# SonoluxV1.net
KiCad netlist of a schematic drawn in EAGLE
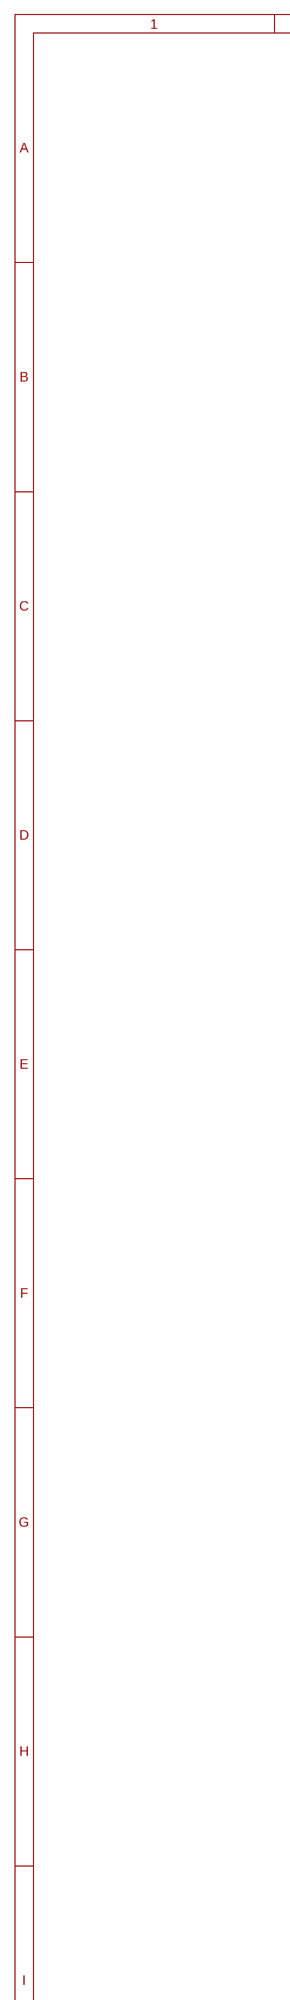
[diagram p0: schematic, sheet 1, part 1 of 2]
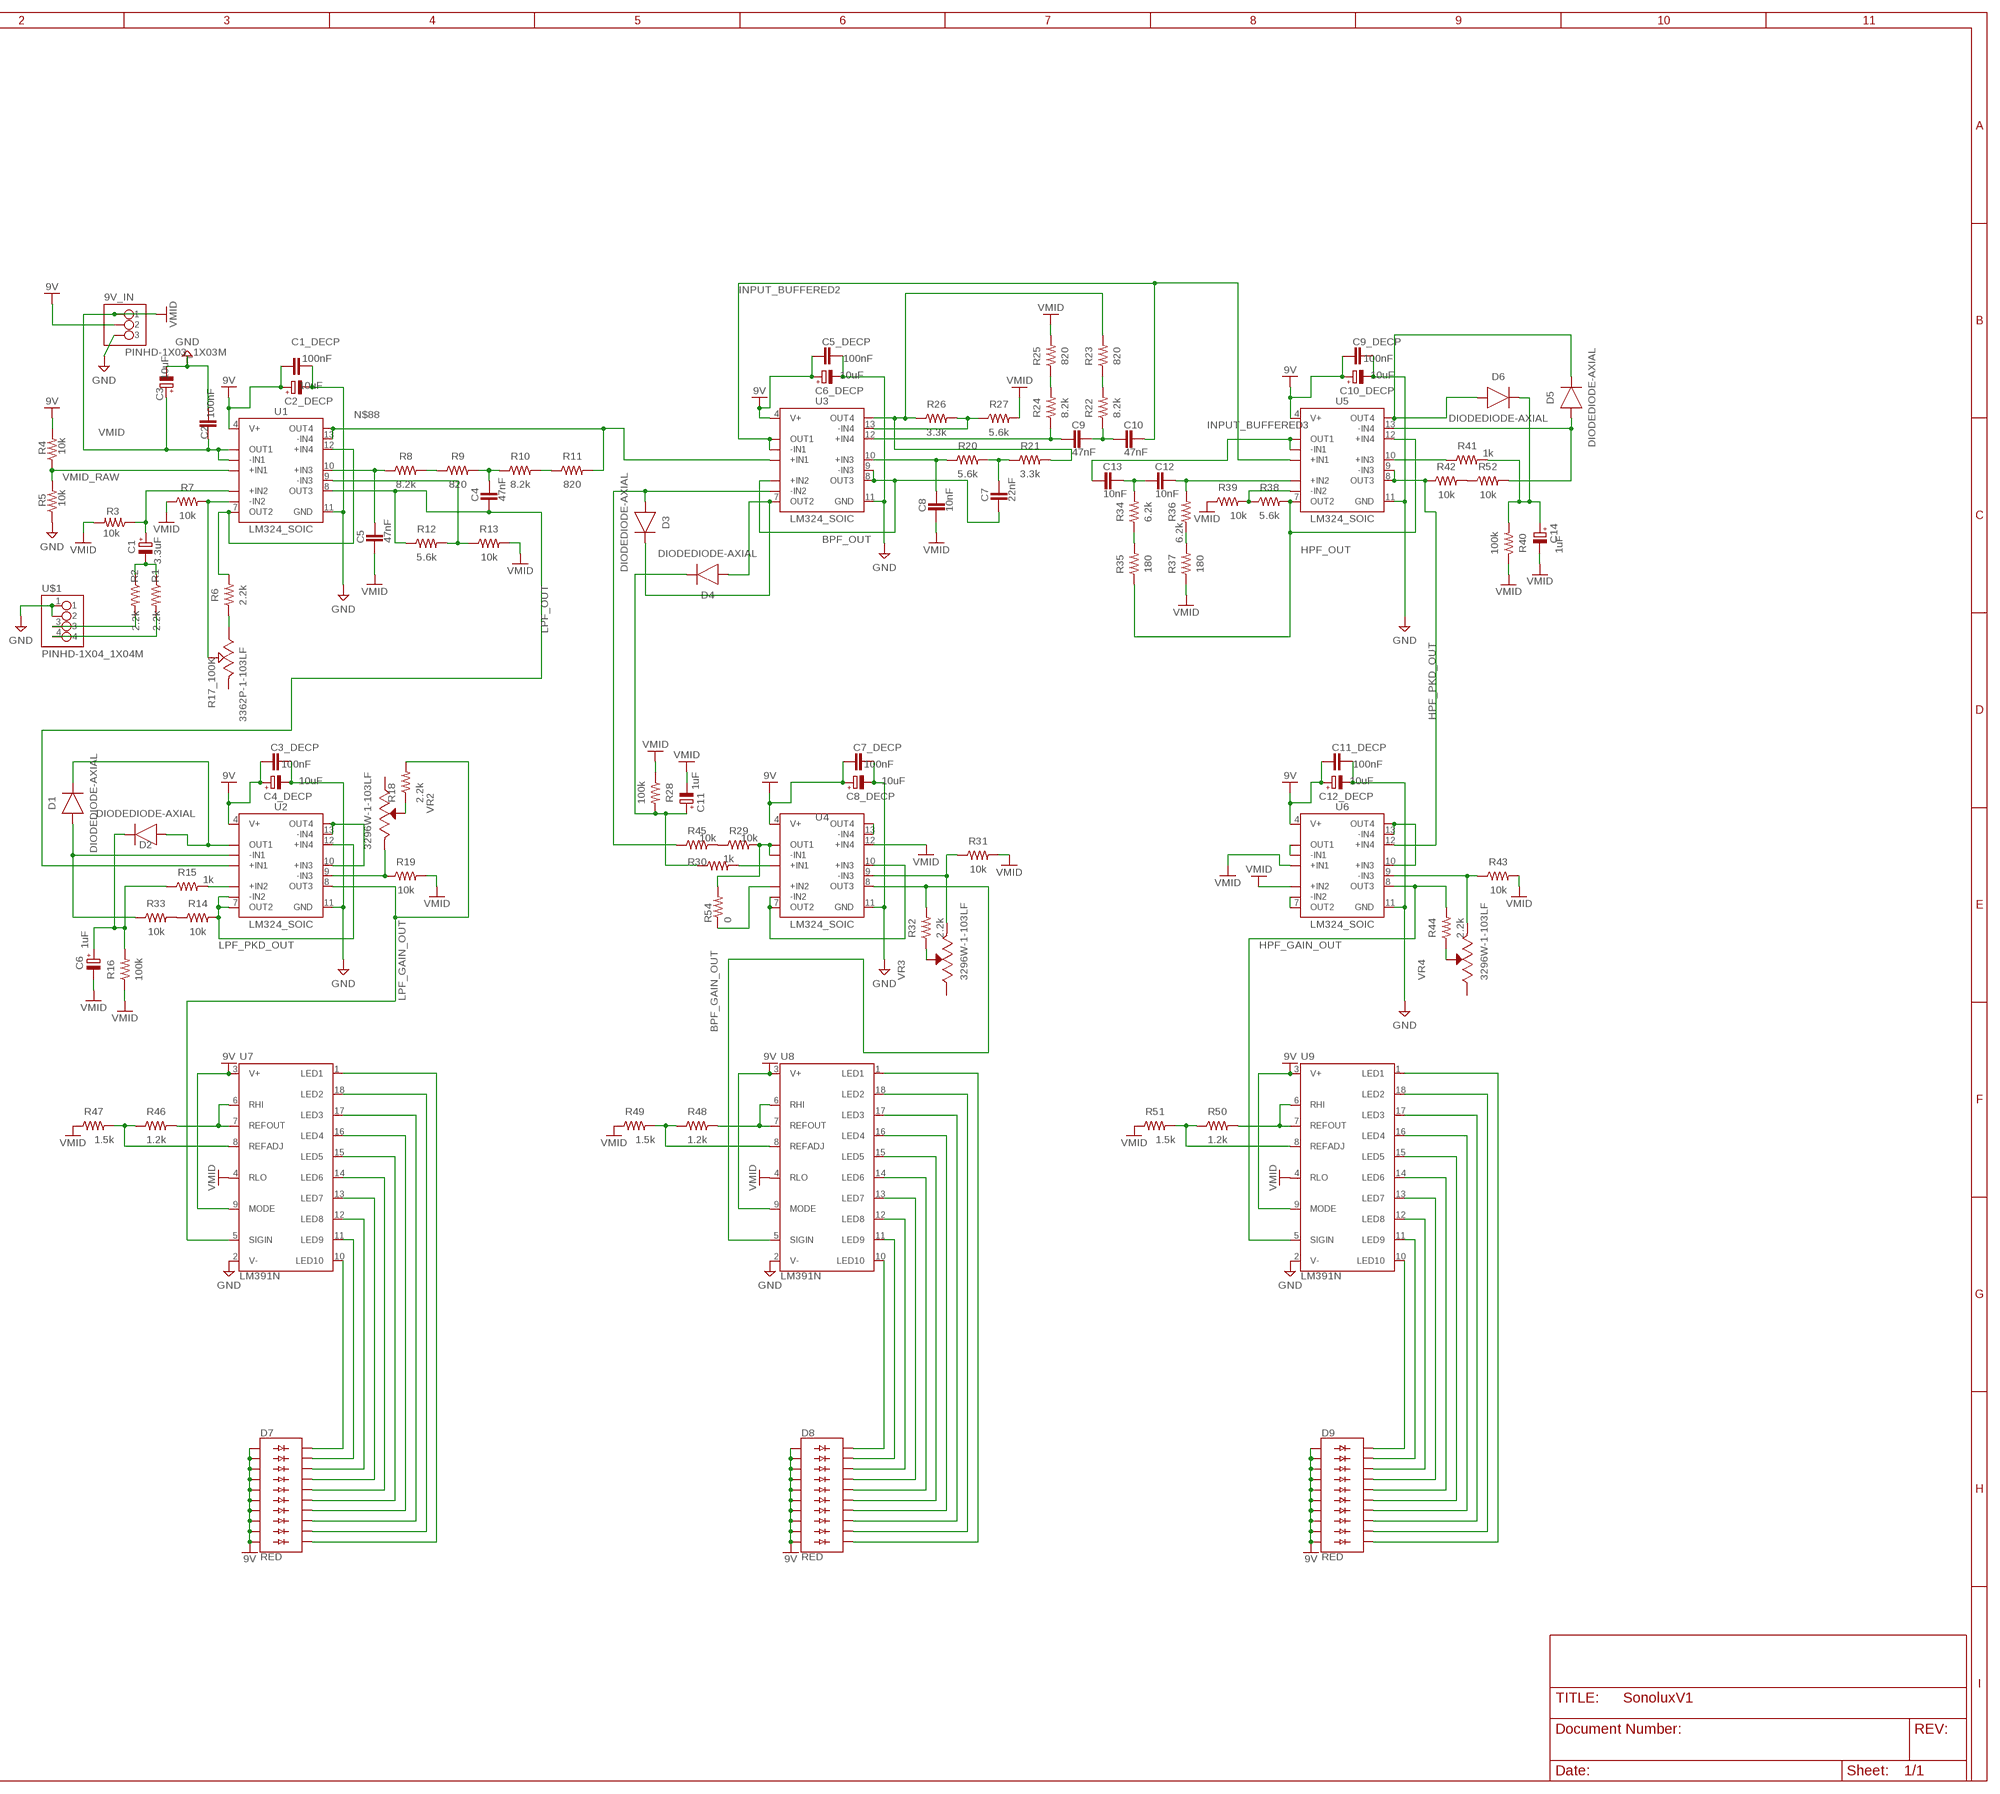
[diagram p1: schematic, sheet 1, part 2 of 2]

(export (version "E")
  (design (tool "Eeschema 10.0.6"))
  (components
    (comp (ref "9V_IN")
      (value "PINHD-1X03_1X03M")
      (footprint "eagle-import:1X03")
      (libsource (lib "eagle-import") (part "PINHD-1X03_1X03M"))
    )
    (comp (ref "C1")
      (value "3.3uF")
      (footprint "eagle-import:CAPPRD254W65D500H1150B")
      (libsource (lib "eagle-import") (part "CAPACITOR-POLRADIAL-5MM-DIA"))
    )
    (comp (ref "C1_DECP")
      (value "100nF")
      (footprint "eagle-import:CAP-THRU-2.54MM")
      (libsource (lib "eagle-import") (part "CAPACITORCERAMIC-2.54MM"))
    )
    (comp (ref "C2")
      (value "100nF")
      (footprint "eagle-import:CAP-THRU-2.54MM")
      (libsource (lib "eagle-import") (part "CAPACITORCERAMIC-2.54MM"))
    )
    (comp (ref "C2_DECP")
      (value "10uF")
      (footprint "eagle-import:CAPPRD254W65D500H1150B")
      (libsource (lib "eagle-import") (part "CAPACITOR-POLRADIAL-5MM-DIA"))
    )
    (comp (ref "C3")
      (value "10uF")
      (footprint "eagle-import:CAPPRD254W65D500H1150B")
      (libsource (lib "eagle-import") (part "CAPACITOR-POLRADIAL-5MM-DIA"))
    )
    (comp (ref "C3_DECP")
      (value "100nF")
      (footprint "eagle-import:CAP-THRU-2.54MM")
      (libsource (lib "eagle-import") (part "CAPACITORCERAMIC-2.54MM"))
    )
    (comp (ref "C4")
      (value "47nF")
      (footprint "eagle-import:CAP-THRU-2.54MM")
      (libsource (lib "eagle-import") (part "CAPACITORCERAMIC-2.54MM"))
    )
    (comp (ref "C4_DECP")
      (value "10uF")
      (footprint "eagle-import:CAPPRD254W65D500H1150B")
      (libsource (lib "eagle-import") (part "CAPACITOR-POLRADIAL-5MM-DIA"))
    )
    (comp (ref "C5")
      (value "47nF")
      (footprint "eagle-import:CAP-THRU-2.54MM")
      (libsource (lib "eagle-import") (part "CAPACITORCERAMIC-2.54MM"))
    )
    (comp (ref "C5_DECP")
      (value "100nF")
      (footprint "eagle-import:CAP-THRU-2.54MM")
      (libsource (lib "eagle-import") (part "CAPACITORCERAMIC-2.54MM"))
    )
    (comp (ref "C6")
      (value "1uF")
      (footprint "eagle-import:CAPPRD254W65D500H1150B")
      (libsource (lib "eagle-import") (part "CAPACITOR-POLRADIAL-5MM-DIA"))
    )
    (comp (ref "C6_DECP")
      (value "10uF")
      (footprint "eagle-import:CAPPRD254W65D500H1150B")
      (libsource (lib "eagle-import") (part "CAPACITOR-POLRADIAL-5MM-DIA"))
    )
    (comp (ref "C7")
      (value "22nF")
      (footprint "eagle-import:CAP-THRU-2.54MM")
      (libsource (lib "eagle-import") (part "CAPACITORCERAMIC-2.54MM"))
    )
    (comp (ref "C7_DECP")
      (value "100nF")
      (footprint "eagle-import:CAP-THRU-2.54MM")
      (libsource (lib "eagle-import") (part "CAPACITORCERAMIC-2.54MM"))
    )
    (comp (ref "C8")
      (value "10nF")
      (footprint "eagle-import:CAP-THRU-2.54MM")
      (libsource (lib "eagle-import") (part "CAPACITORCERAMIC-2.54MM"))
    )
    (comp (ref "C8_DECP")
      (value "10uF")
      (footprint "eagle-import:CAPPRD254W65D500H1150B")
      (libsource (lib "eagle-import") (part "CAPACITOR-POLRADIAL-5MM-DIA"))
    )
    (comp (ref "C9")
      (value "47nF")
      (footprint "eagle-import:CAP-THRU-2.54MM")
      (libsource (lib "eagle-import") (part "CAPACITORCERAMIC-2.54MM"))
    )
    (comp (ref "C9_DECP")
      (value "100nF")
      (footprint "eagle-import:CAP-THRU-2.54MM")
      (libsource (lib "eagle-import") (part "CAPACITORCERAMIC-2.54MM"))
    )
    (comp (ref "C10")
      (value "47nF")
      (footprint "eagle-import:CAP-THRU-2.54MM")
      (libsource (lib "eagle-import") (part "CAPACITORCERAMIC-2.54MM"))
    )
    (comp (ref "C10_DECP")
      (value "10uF")
      (footprint "eagle-import:CAPPRD254W65D500H1150B")
      (libsource (lib "eagle-import") (part "CAPACITOR-POLRADIAL-5MM-DIA"))
    )
    (comp (ref "C11")
      (value "1uF")
      (footprint "eagle-import:CAPPRD254W65D500H1150B")
      (libsource (lib "eagle-import") (part "CAPACITOR-POLRADIAL-5MM-DIA"))
    )
    (comp (ref "C11_DECP")
      (value "100nF")
      (footprint "eagle-import:CAP-THRU-2.54MM")
      (libsource (lib "eagle-import") (part "CAPACITORCERAMIC-2.54MM"))
    )
    (comp (ref "C12")
      (value "10nF")
      (footprint "eagle-import:CAP-THRU-2.54MM")
      (libsource (lib "eagle-import") (part "CAPACITORCERAMIC-2.54MM"))
    )
    (comp (ref "C12_DECP")
      (value "10uF")
      (footprint "eagle-import:CAPPRD254W65D500H1150B")
      (libsource (lib "eagle-import") (part "CAPACITOR-POLRADIAL-5MM-DIA"))
    )
    (comp (ref "C13")
      (value "10nF")
      (footprint "eagle-import:CAP-THRU-2.54MM")
      (libsource (lib "eagle-import") (part "CAPACITORCERAMIC-2.54MM"))
    )
    (comp (ref "C14")
      (value "1uF")
      (footprint "eagle-import:CAPPRD254W65D500H1150B")
      (libsource (lib "eagle-import") (part "CAPACITOR-POLRADIAL-5MM-DIA"))
    )
    (comp (ref "D1")
      (value "DIODEDIODE-AXIAL")
      (footprint "eagle-import:DIODE-AXIAL")
      (libsource (lib "eagle-import") (part "DIODEDIODE-AXIAL"))
    )
    (comp (ref "D2")
      (value "DIODEDIODE-AXIAL")
      (footprint "eagle-import:DIODE-AXIAL")
      (libsource (lib "eagle-import") (part "DIODEDIODE-AXIAL"))
    )
    (comp (ref "D3")
      (value "DIODEDIODE-AXIAL")
      (footprint "eagle-import:DIODE-AXIAL")
      (libsource (lib "eagle-import") (part "DIODEDIODE-AXIAL"))
    )
    (comp (ref "D4")
      (value "DIODEDIODE-AXIAL")
      (footprint "eagle-import:DIODE-AXIAL")
      (libsource (lib "eagle-import") (part "DIODEDIODE-AXIAL"))
    )
    (comp (ref "D5")
      (value "DIODEDIODE-AXIAL")
      (footprint "eagle-import:DIODE-AXIAL")
      (libsource (lib "eagle-import") (part "DIODEDIODE-AXIAL"))
    )
    (comp (ref "D6")
      (value "DIODEDIODE-AXIAL")
      (footprint "eagle-import:DIODE-AXIAL")
      (libsource (lib "eagle-import") (part "DIODEDIODE-AXIAL"))
    )
    (comp (ref "D7")
      (value "RED")
      (footprint "eagle-import:LED_BARGRAPH_10")
      (libsource (lib "eagle-import") (part "LED_BARGRAPH_10RED"))
    )
    (comp (ref "D8")
      (value "RED")
      (footprint "eagle-import:LED_BARGRAPH_10")
      (libsource (lib "eagle-import") (part "LED_BARGRAPH_10RED"))
    )
    (comp (ref "D9")
      (value "RED")
      (footprint "eagle-import:LED_BARGRAPH_10")
      (libsource (lib "eagle-import") (part "LED_BARGRAPH_10RED"))
    )
    (comp (ref "R1")
      (value "2.2k")
      (footprint "eagle-import:RESAD724W46L381D178B")
      (libsource (lib "eagle-import") (part "Tutorial - Fusion 360_16997205_R-USAXIAL-7.2MM-PITCH_"))
    )
    (comp (ref "R2")
      (value "2.2k")
      (footprint "eagle-import:RESAD724W46L381D178B")
      (libsource (lib "eagle-import") (part "Tutorial - Fusion 360_16997205_R-USAXIAL-7.2MM-PITCH_"))
    )
    (comp (ref "R3")
      (value "10k")
      (footprint "eagle-import:RESAD724W46L381D178B")
      (libsource (lib "eagle-import") (part "Tutorial - Fusion 360_16997205_R-USAXIAL-7.2MM-PITCH_"))
    )
    (comp (ref "R4")
      (value "10k")
      (footprint "eagle-import:RESAD724W46L381D178B")
      (libsource (lib "eagle-import") (part "Tutorial - Fusion 360_16997205_R-USAXIAL-7.2MM-PITCH_"))
    )
    (comp (ref "R5")
      (value "10k")
      (footprint "eagle-import:RESAD724W46L381D178B")
      (libsource (lib "eagle-import") (part "Tutorial - Fusion 360_16997205_R-USAXIAL-7.2MM-PITCH_"))
    )
    (comp (ref "R6")
      (value "2.2k")
      (footprint "eagle-import:RESAD724W46L381D178B")
      (libsource (lib "eagle-import") (part "R-USAXIAL-7.2MM-PITCH_"))
    )
    (comp (ref "R7")
      (value "10k")
      (footprint "eagle-import:RESAD724W46L381D178B")
      (libsource (lib "eagle-import") (part "R-USAXIAL-7.2MM-PITCH_"))
    )
    (comp (ref "R8")
      (value "8.2k")
      (footprint "eagle-import:RESAD724W46L381D178B")
      (libsource (lib "eagle-import") (part "R-USAXIAL-7.2MM-PITCH_"))
    )
    (comp (ref "R9")
      (value "820")
      (footprint "eagle-import:RESAD724W46L381D178B")
      (libsource (lib "eagle-import") (part "R-USAXIAL-7.2MM-PITCH_"))
    )
    (comp (ref "R10")
      (value "8.2k")
      (footprint "eagle-import:RESAD724W46L381D178B")
      (libsource (lib "eagle-import") (part "R-USAXIAL-7.2MM-PITCH_"))
    )
    (comp (ref "R11")
      (value "820")
      (footprint "eagle-import:RESAD724W46L381D178B")
      (libsource (lib "eagle-import") (part "R-USAXIAL-7.2MM-PITCH_"))
    )
    (comp (ref "R12")
      (value "5.6k")
      (footprint "eagle-import:RESAD724W46L381D178B")
      (libsource (lib "eagle-import") (part "R-USAXIAL-7.2MM-PITCH_"))
    )
    (comp (ref "R13")
      (value "10k")
      (footprint "eagle-import:RESAD724W46L381D178B")
      (libsource (lib "eagle-import") (part "R-USAXIAL-7.2MM-PITCH_"))
    )
    (comp (ref "R14")
      (value "10k")
      (footprint "eagle-import:RESAD724W46L381D178B")
      (libsource (lib "eagle-import") (part "R-USAXIAL-7.2MM-PITCH_"))
    )
    (comp (ref "R15")
      (value "1k")
      (footprint "eagle-import:RESAD724W46L381D178B")
      (libsource (lib "eagle-import") (part "R-USAXIAL-7.2MM-PITCH_"))
    )
    (comp (ref "R16")
      (value "100k")
      (footprint "eagle-import:RESAD724W46L381D178B")
      (libsource (lib "eagle-import") (part "R-USAXIAL-7.2MM-PITCH_"))
    )
    (comp (ref "R17_100K")
      (value "3362P-1-103LF")
      (footprint "eagle-import:3362P-1-103LF")
      (fields (field (name "MANUFACTURER") "Bourns Inc.") (field (name "CREATED_PN") "PCBLayout.com"))
      (libsource (lib "eagle-import") (part "3362P-1-103LF"))
    )
    (comp (ref "R18")
      (value "2.2k")
      (footprint "eagle-import:RESAD724W46L381D178B")
      (libsource (lib "eagle-import") (part "R-USAXIAL-7.2MM-PITCH_"))
    )
    (comp (ref "R19")
      (value "10k")
      (footprint "eagle-import:RESAD724W46L381D178B")
      (libsource (lib "eagle-import") (part "R-USAXIAL-7.2MM-PITCH_"))
    )
    (comp (ref "R20")
      (value "5.6k")
      (footprint "eagle-import:RESAD724W46L381D178B")
      (libsource (lib "eagle-import") (part "R-USAXIAL-7.2MM-PITCH_"))
    )
    (comp (ref "R21")
      (value "3.3k")
      (footprint "eagle-import:RESAD724W46L381D178B")
      (libsource (lib "eagle-import") (part "R-USAXIAL-7.2MM-PITCH_"))
    )
    (comp (ref "R22")
      (value "8.2k")
      (footprint "eagle-import:RESAD724W46L381D178B")
      (libsource (lib "eagle-import") (part "R-USAXIAL-7.2MM-PITCH_"))
    )
    (comp (ref "R23")
      (value "820")
      (footprint "eagle-import:RESAD724W46L381D178B")
      (libsource (lib "eagle-import") (part "R-USAXIAL-7.2MM-PITCH_"))
    )
    (comp (ref "R24")
      (value "8.2k")
      (footprint "eagle-import:RESAD724W46L381D178B")
      (libsource (lib "eagle-import") (part "R-USAXIAL-7.2MM-PITCH_"))
    )
    (comp (ref "R25")
      (value "820")
      (footprint "eagle-import:RESAD724W46L381D178B")
      (libsource (lib "eagle-import") (part "R-USAXIAL-7.2MM-PITCH_"))
    )
    (comp (ref "R26")
      (value "3.3k")
      (footprint "eagle-import:RESAD724W46L381D178B")
      (libsource (lib "eagle-import") (part "R-USAXIAL-7.2MM-PITCH_"))
    )
    (comp (ref "R27")
      (value "5.6k")
      (footprint "eagle-import:RESAD724W46L381D178B")
      (libsource (lib "eagle-import") (part "R-USAXIAL-7.2MM-PITCH_"))
    )
    (comp (ref "R28")
      (value "100k")
      (footprint "eagle-import:RESAD724W46L381D178B")
      (libsource (lib "eagle-import") (part "R-USAXIAL-7.2MM-PITCH_"))
    )
    (comp (ref "R29")
      (value "10k")
      (footprint "eagle-import:RESAD724W46L381D178B")
      (libsource (lib "eagle-import") (part "R-USAXIAL-7.2MM-PITCH_"))
    )
    (comp (ref "R30")
      (value "1k")
      (footprint "eagle-import:RESAD724W46L381D178B")
      (libsource (lib "eagle-import") (part "R-USAXIAL-7.2MM-PITCH_"))
    )
    (comp (ref "R31")
      (value "10k")
      (footprint "eagle-import:RESAD724W46L381D178B")
      (libsource (lib "eagle-import") (part "R-USAXIAL-7.2MM-PITCH_"))
    )
    (comp (ref "R32")
      (value "2.2k")
      (footprint "eagle-import:RESAD724W46L381D178B")
      (libsource (lib "eagle-import") (part "R-USAXIAL-7.2MM-PITCH_"))
    )
    (comp (ref "R33")
      (value "10k")
      (footprint "eagle-import:RESAD724W46L381D178B")
      (libsource (lib "eagle-import") (part "R-USAXIAL-7.2MM-PITCH_"))
    )
    (comp (ref "R34")
      (value "6.2k")
      (footprint "eagle-import:RESAD724W46L381D178B")
      (libsource (lib "eagle-import") (part "R-USAXIAL-7.2MM-PITCH_"))
    )
    (comp (ref "R35")
      (value "180")
      (footprint "eagle-import:RESAD724W46L381D178B")
      (libsource (lib "eagle-import") (part "R-USAXIAL-7.2MM-PITCH_"))
    )
    (comp (ref "R36")
      (value "6.2k")
      (footprint "eagle-import:RESAD724W46L381D178B")
      (libsource (lib "eagle-import") (part "R-USAXIAL-7.2MM-PITCH_"))
    )
    (comp (ref "R37")
      (value "180")
      (footprint "eagle-import:RESAD724W46L381D178B")
      (libsource (lib "eagle-import") (part "R-USAXIAL-7.2MM-PITCH_"))
    )
    (comp (ref "R38")
      (value "5.6k")
      (footprint "eagle-import:RESAD724W46L381D178B")
      (libsource (lib "eagle-import") (part "R-USAXIAL-7.2MM-PITCH_"))
    )
    (comp (ref "R39")
      (value "10k")
      (footprint "eagle-import:RESAD724W46L381D178B")
      (libsource (lib "eagle-import") (part "R-USAXIAL-7.2MM-PITCH_"))
    )
    (comp (ref "R40")
      (value "100k")
      (footprint "eagle-import:RESAD724W46L381D178B")
      (libsource (lib "eagle-import") (part "R-USAXIAL-7.2MM-PITCH_"))
    )
    (comp (ref "R41")
      (value "1k")
      (footprint "eagle-import:RESAD724W46L381D178B")
      (libsource (lib "eagle-import") (part "R-USAXIAL-7.2MM-PITCH_"))
    )
    (comp (ref "R42")
      (value "10k")
      (footprint "eagle-import:RESAD724W46L381D178B")
      (libsource (lib "eagle-import") (part "R-USAXIAL-7.2MM-PITCH_"))
    )
    (comp (ref "R43")
      (value "10k")
      (footprint "eagle-import:RESAD724W46L381D178B")
      (libsource (lib "eagle-import") (part "R-USAXIAL-7.2MM-PITCH_"))
    )
    (comp (ref "R44")
      (value "2.2k")
      (footprint "eagle-import:RESAD724W46L381D178B")
      (libsource (lib "eagle-import") (part "R-USAXIAL-7.2MM-PITCH_"))
    )
    (comp (ref "R45")
      (value "10k")
      (footprint "eagle-import:RESAD724W46L381D178B")
      (libsource (lib "eagle-import") (part "R-USAXIAL-7.2MM-PITCH_"))
    )
    (comp (ref "R46")
      (value "1.2k")
      (footprint "eagle-import:RESAD724W46L381D178B")
      (libsource (lib "eagle-import") (part "R-USAXIAL-7.2MM-PITCH_"))
    )
    (comp (ref "R47")
      (value "1.5k")
      (footprint "eagle-import:RESAD724W46L381D178B")
      (libsource (lib "eagle-import") (part "R-USAXIAL-7.2MM-PITCH_"))
    )
    (comp (ref "R48")
      (value "1.2k")
      (footprint "eagle-import:RESAD724W46L381D178B")
      (libsource (lib "eagle-import") (part "R-USAXIAL-7.2MM-PITCH_"))
    )
    (comp (ref "R49")
      (value "1.5k")
      (footprint "eagle-import:RESAD724W46L381D178B")
      (libsource (lib "eagle-import") (part "R-USAXIAL-7.2MM-PITCH_"))
    )
    (comp (ref "R50")
      (value "1.2k")
      (footprint "eagle-import:RESAD724W46L381D178B")
      (libsource (lib "eagle-import") (part "R-USAXIAL-7.2MM-PITCH_"))
    )
    (comp (ref "R51")
      (value "1.5k")
      (footprint "eagle-import:RESAD724W46L381D178B")
      (libsource (lib "eagle-import") (part "R-USAXIAL-7.2MM-PITCH_"))
    )
    (comp (ref "R52")
      (value "10k")
      (footprint "eagle-import:RESAD724W46L381D178B")
      (libsource (lib "eagle-import") (part "R-USAXIAL-7.2MM-PITCH_"))
    )
    (comp (ref "R54")
      (value "0")
      (footprint "eagle-import:RESAD724W46L381D178B")
      (libsource (lib "eagle-import") (part "Tutorial - Fusion 360_16997205_R-USAXIAL-7.2MM-PITCH_"))
    )
    (comp (ref "U$1")
      (value "PINHD-1X04_1X04M")
      (footprint "eagle-import:1X04")
      (libsource (lib "eagle-import") (part "PINHD-1X04_1X04M"))
    )
    (comp (ref "U1")
      (value "LM324_SOIC")
      (footprint "eagle-import:SOIC127P600X175-14N")
      (libsource (lib "eagle-import") (part "LM324_SOIC"))
    )
    (comp (ref "U2")
      (value "LM324_SOIC")
      (footprint "eagle-import:SOIC127P600X175-14N")
      (libsource (lib "eagle-import") (part "LM324_SOIC"))
    )
    (comp (ref "U3")
      (value "LM324_SOIC")
      (footprint "eagle-import:SOIC127P600X175-14N")
      (libsource (lib "eagle-import") (part "LM324_SOIC"))
    )
    (comp (ref "U4")
      (value "LM324_SOIC")
      (footprint "eagle-import:SOIC127P600X175-14N")
      (libsource (lib "eagle-import") (part "LM324_SOIC"))
    )
    (comp (ref "U5")
      (value "LM324_SOIC")
      (footprint "eagle-import:SOIC127P600X175-14N")
      (libsource (lib "eagle-import") (part "LM324_SOIC"))
    )
    (comp (ref "U6")
      (value "LM324_SOIC")
      (footprint "eagle-import:SOIC127P600X175-14N")
      (libsource (lib "eagle-import") (part "LM324_SOIC"))
    )
    (comp (ref "U7")
      (value "LM391N")
      (footprint "eagle-import:DIL18")
      (libsource (lib "eagle-import") (part "LM391N"))
    )
    (comp (ref "U8")
      (value "LM391N")
      (footprint "eagle-import:DIL18")
      (libsource (lib "eagle-import") (part "LM391N"))
    )
    (comp (ref "U9")
      (value "LM391N")
      (footprint "eagle-import:DIL18")
      (libsource (lib "eagle-import") (part "LM391N"))
    )
    (comp (ref "VR2")
      (value "3296W-1-103LF")
      (footprint "eagle-import:TRIM_3296W-1-103LF")
      (fields (field (name "MF") "Bourns"))
      (libsource (lib "eagle-import") (part "3296W-1-103LF"))
    )
    (comp (ref "VR3")
      (value "3296W-1-103LF")
      (footprint "eagle-import:TRIM_3296W-1-103LF")
      (fields (field (name "MF") "Bourns"))
      (libsource (lib "eagle-import") (part "3296W-1-103LF"))
    )
    (comp (ref "VR4")
      (value "3296W-1-103LF")
      (footprint "eagle-import:TRIM_3296W-1-103LF")
      (fields (field (name "MF") "Bourns"))
      (libsource (lib "eagle-import") (part "3296W-1-103LF"))
    )
  )
  (nets
    (net (code "1") (name "/BPF_GAIN_OUT") (class "Default")
      (node (ref "R32") (pin "2") (pinfunction "2_2") (pintype "passive"))
      (node (ref "U4") (pin "8") (pinfunction "OUT3_8") (pintype "passive"))
      (node (ref "U8") (pin "5") (pinfunction "SIGIN_5") (pintype "input"))
    )
    (net (code "2") (name "/BPF_OUT") (class "Default")
      (node (ref "C7") (pin "2") (pinfunction "2_2") (pintype "passive"))
      (node (ref "U3") (pin "5") (pinfunction "+IN2_5") (pintype "passive"))
      (node (ref "U3") (pin "8") (pinfunction "OUT3_8") (pintype "passive"))
      (node (ref "U3") (pin "9") (pinfunction "-IN3_9") (pintype "passive"))
    )
    (net (code "3") (name "/HPF_GAIN_OUT") (class "Default")
      (node (ref "R44") (pin "2") (pinfunction "2_2") (pintype "passive"))
      (node (ref "U6") (pin "8") (pinfunction "OUT3_8") (pintype "passive"))
      (node (ref "U9") (pin "5") (pinfunction "SIGIN_5") (pintype "input"))
    )
    (net (code "4") (name "/HPF_OUT") (class "Default")
      (node (ref "R35") (pin "1") (pinfunction "1_1") (pintype "passive"))
      (node (ref "R38") (pin "2") (pinfunction "2_2") (pintype "passive"))
      (node (ref "U5") (pin "12") (pinfunction "+IN4_12") (pintype "bidirectional"))
      (node (ref "U5") (pin "7") (pinfunction "OUT2_7") (pintype "passive"))
    )
    (net (code "5") (name "/HPF_PKD_OUT") (class "Default")
      (node (ref "R42") (pin "1") (pinfunction "1_1") (pintype "passive"))
      (node (ref "U5") (pin "8") (pinfunction "OUT3_8") (pintype "passive"))
      (node (ref "U5") (pin "9") (pinfunction "-IN3_9") (pintype "passive"))
      (node (ref "U6") (pin "12") (pinfunction "+IN4_12") (pintype "bidirectional"))
    )
    (net (code "6") (name "/INPUT_BUFFERED2") (class "Default")
      (node (ref "C10") (pin "1") (pinfunction "1_1") (pintype "passive"))
      (node (ref "U3") (pin "1") (pinfunction "OUT1_1") (pintype "input"))
      (node (ref "U3") (pin "2") (pinfunction "-IN1_2") (pintype "input"))
      (node (ref "U5") (pin "3") (pinfunction "+IN1_3") (pintype "bidirectional"))
    )
    (net (code "7") (name "/INPUT_BUFFERED3") (class "Default")
      (node (ref "C13") (pin "2") (pinfunction "2_2") (pintype "passive"))
      (node (ref "U5") (pin "1") (pinfunction "OUT1_1") (pintype "input"))
      (node (ref "U5") (pin "2") (pinfunction "-IN1_2") (pintype "input"))
    )
    (net (code "8") (name "/LPF_GAIN_OUT") (class "Default")
      (node (ref "R18") (pin "2") (pinfunction "2_2") (pintype "passive"))
      (node (ref "U2") (pin "8") (pinfunction "OUT3_8") (pintype "passive"))
      (node (ref "U7") (pin "5") (pinfunction "SIGIN_5") (pintype "input"))
    )
    (net (code "9") (name "/LPF_OUT") (class "Default")
      (node (ref "C4") (pin "2") (pinfunction "2_2") (pintype "passive"))
      (node (ref "R12") (pin "1") (pinfunction "1_1") (pintype "passive"))
      (node (ref "U1") (pin "8") (pinfunction "OUT3_8") (pintype "passive"))
      (node (ref "U2") (pin "3") (pinfunction "+IN1_3") (pintype "bidirectional"))
    )
    (net (code "10") (name "/LPF_PKD_OUT") (class "Default")
      (node (ref "R14") (pin "2") (pinfunction "2_2") (pintype "passive"))
      (node (ref "U2") (pin "12") (pinfunction "+IN4_12") (pintype "bidirectional"))
      (node (ref "U2") (pin "6") (pinfunction "-IN2_6") (pintype "passive"))
      (node (ref "U2") (pin "7") (pinfunction "OUT2_7") (pintype "passive"))
    )
    (net (code "11") (name "/N$88") (class "Default")
      (node (ref "R11") (pin "2") (pinfunction "2_2") (pintype "passive"))
      (node (ref "U1") (pin "13") (pinfunction "-IN4_13") (pintype "bidirectional"))
      (node (ref "U1") (pin "14") (pinfunction "OUT4_14") (pintype "output"))
      (node (ref "U3") (pin "3") (pinfunction "+IN1_3") (pintype "bidirectional"))
    )
    (net (code "12") (name "/VMID_RAW") (class "Default")
      (node (ref "R4") (pin "1") (pinfunction "1_1") (pintype "passive"))
      (node (ref "R5") (pin "2") (pinfunction "2_2") (pintype "passive"))
      (node (ref "U1") (pin "3") (pinfunction "+IN1_3") (pintype "bidirectional"))
    )
    (net (code "13") (name "9V") (class "Default")
      (node (ref "9V_IN") (pin "2") (pinfunction "2_2") (pintype "bidirectional"))
      (node (ref "C10_DECP") (pin "1") (pinfunction "+_1") (pintype "passive"))
      (node (ref "C11_DECP") (pin "2") (pinfunction "2_2") (pintype "passive"))
      (node (ref "C12_DECP") (pin "1") (pinfunction "+_1") (pintype "passive"))
      (node (ref "C1_DECP") (pin "2") (pinfunction "2_2") (pintype "passive"))
      (node (ref "C2_DECP") (pin "1") (pinfunction "+_1") (pintype "passive"))
      (node (ref "C3_DECP") (pin "2") (pinfunction "2_2") (pintype "passive"))
      (node (ref "C4_DECP") (pin "1") (pinfunction "+_1") (pintype "passive"))
      (node (ref "C5_DECP") (pin "2") (pinfunction "2_2") (pintype "passive"))
      (node (ref "C6_DECP") (pin "1") (pinfunction "+_1") (pintype "passive"))
      (node (ref "C7_DECP") (pin "2") (pinfunction "2_2") (pintype "passive"))
      (node (ref "C8_DECP") (pin "1") (pinfunction "+_1") (pintype "passive"))
      (node (ref "C9_DECP") (pin "2") (pinfunction "2_2") (pintype "passive"))
      (node (ref "D7") (pin "1") (pinfunction "A_1") (pintype "passive"))
      (node (ref "D7") (pin "10") (pinfunction "A9_10") (pintype "passive"))
      (node (ref "D7") (pin "2") (pinfunction "A1_2") (pintype "passive"))
      (node (ref "D7") (pin "3") (pinfunction "A2_3") (pintype "passive"))
      (node (ref "D7") (pin "4") (pinfunction "A3_4") (pintype "passive"))
      (node (ref "D7") (pin "5") (pinfunction "A4_5") (pintype "passive"))
      (node (ref "D7") (pin "6") (pinfunction "A5_6") (pintype "passive"))
      (node (ref "D7") (pin "7") (pinfunction "A6_7") (pintype "passive"))
      (node (ref "D7") (pin "8") (pinfunction "A7_8") (pintype "passive"))
      (node (ref "D7") (pin "9") (pinfunction "A8_9") (pintype "passive"))
      (node (ref "D8") (pin "1") (pinfunction "A_1") (pintype "passive"))
      (node (ref "D8") (pin "10") (pinfunction "A9_10") (pintype "passive"))
      (node (ref "D8") (pin "2") (pinfunction "A1_2") (pintype "passive"))
      (node (ref "D8") (pin "3") (pinfunction "A2_3") (pintype "passive"))
      (node (ref "D8") (pin "4") (pinfunction "A3_4") (pintype "passive"))
      (node (ref "D8") (pin "5") (pinfunction "A4_5") (pintype "passive"))
      (node (ref "D8") (pin "6") (pinfunction "A5_6") (pintype "passive"))
      (node (ref "D8") (pin "7") (pinfunction "A6_7") (pintype "passive"))
      (node (ref "D8") (pin "8") (pinfunction "A7_8") (pintype "passive"))
      (node (ref "D8") (pin "9") (pinfunction "A8_9") (pintype "passive"))
      (node (ref "D9") (pin "1") (pinfunction "A_1") (pintype "passive"))
      (node (ref "D9") (pin "10") (pinfunction "A9_10") (pintype "passive"))
      (node (ref "D9") (pin "2") (pinfunction "A1_2") (pintype "passive"))
      (node (ref "D9") (pin "3") (pinfunction "A2_3") (pintype "passive"))
      (node (ref "D9") (pin "4") (pinfunction "A3_4") (pintype "passive"))
      (node (ref "D9") (pin "5") (pinfunction "A4_5") (pintype "passive"))
      (node (ref "D9") (pin "6") (pinfunction "A5_6") (pintype "passive"))
      (node (ref "D9") (pin "7") (pinfunction "A6_7") (pintype "passive"))
      (node (ref "D9") (pin "8") (pinfunction "A7_8") (pintype "passive"))
      (node (ref "D9") (pin "9") (pinfunction "A8_9") (pintype "passive"))
      (node (ref "R4") (pin "2") (pinfunction "2_2") (pintype "passive"))
      (node (ref "U1") (pin "4") (pinfunction "V+_4") (pintype "passive"))
      (node (ref "U2") (pin "4") (pinfunction "V+_4") (pintype "passive"))
      (node (ref "U3") (pin "4") (pinfunction "V+_4") (pintype "passive"))
      (node (ref "U4") (pin "4") (pinfunction "V+_4") (pintype "passive"))
      (node (ref "U5") (pin "4") (pinfunction "V+_4") (pintype "passive"))
      (node (ref "U6") (pin "4") (pinfunction "V+_4") (pintype "passive"))
      (node (ref "U7") (pin "3") (pinfunction "V+_3") (pintype "power_in"))
      (node (ref "U7") (pin "9") (pinfunction "MODE_9") (pintype "input"))
      (node (ref "U8") (pin "3") (pinfunction "V+_3") (pintype "power_in"))
      (node (ref "U8") (pin "9") (pinfunction "MODE_9") (pintype "input"))
      (node (ref "U9") (pin "3") (pinfunction "V+_3") (pintype "power_in"))
      (node (ref "U9") (pin "9") (pinfunction "MODE_9") (pintype "input"))
    )
    (net (code "14") (name "GND") (class "Default")
      (node (ref "9V_IN") (pin "3") (pinfunction "3_3") (pintype "bidirectional"))
      (node (ref "C10_DECP") (pin "2") (pinfunction "-_2") (pintype "passive"))
      (node (ref "C11_DECP") (pin "1") (pinfunction "1_1") (pintype "passive"))
      (node (ref "C12_DECP") (pin "2") (pinfunction "-_2") (pintype "passive"))
      (node (ref "C1_DECP") (pin "1") (pinfunction "1_1") (pintype "passive"))
      (node (ref "C2") (pin "1") (pinfunction "1_1") (pintype "passive"))
      (node (ref "C2_DECP") (pin "2") (pinfunction "-_2") (pintype "passive"))
      (node (ref "C3") (pin "2") (pinfunction "-_2") (pintype "passive"))
      (node (ref "C3_DECP") (pin "1") (pinfunction "1_1") (pintype "passive"))
      (node (ref "C4_DECP") (pin "2") (pinfunction "-_2") (pintype "passive"))
      (node (ref "C5_DECP") (pin "1") (pinfunction "1_1") (pintype "passive"))
      (node (ref "C6_DECP") (pin "2") (pinfunction "-_2") (pintype "passive"))
      (node (ref "C7_DECP") (pin "1") (pinfunction "1_1") (pintype "passive"))
      (node (ref "C8_DECP") (pin "2") (pinfunction "-_2") (pintype "passive"))
      (node (ref "C9_DECP") (pin "1") (pinfunction "1_1") (pintype "passive"))
      (node (ref "R5") (pin "1") (pinfunction "1_1") (pintype "passive"))
      (node (ref "U$1") (pin "1") (pinfunction "1_1") (pintype "bidirectional"))
      (node (ref "U$1") (pin "2") (pinfunction "2_2") (pintype "bidirectional"))
      (node (ref "U1") (pin "11") (pinfunction "GND_11") (pintype "passive"))
      (node (ref "U2") (pin "11") (pinfunction "GND_11") (pintype "passive"))
      (node (ref "U3") (pin "11") (pinfunction "GND_11") (pintype "passive"))
      (node (ref "U4") (pin "11") (pinfunction "GND_11") (pintype "passive"))
      (node (ref "U5") (pin "11") (pinfunction "GND_11") (pintype "passive"))
      (node (ref "U6") (pin "11") (pinfunction "GND_11") (pintype "passive"))
      (node (ref "U7") (pin "2") (pinfunction "V-_2") (pintype "power_in"))
      (node (ref "U8") (pin "2") (pinfunction "V-_2") (pintype "power_in"))
      (node (ref "U9") (pin "2") (pinfunction "V-_2") (pintype "power_in"))
    )
    (net (code "15") (name "Net-(C1-+)") (class "Default")
      (node (ref "C1") (pin "1") (pinfunction "+_1") (pintype "passive"))
      (node (ref "R3") (pin "1") (pinfunction "1_1") (pintype "passive"))
      (node (ref "U1") (pin "5") (pinfunction "+IN2_5") (pintype "passive"))
    )
    (net (code "16") (name "Net-(C1--)") (class "Default")
      (node (ref "C1") (pin "2") (pinfunction "-_2") (pintype "passive"))
      (node (ref "R1") (pin "1") (pinfunction "1_1") (pintype "passive"))
      (node (ref "R2") (pin "1") (pinfunction "1_1") (pintype "passive"))
    )
    (net (code "17") (name "Net-(C4-Pad1)") (class "Default")
      (node (ref "C4") (pin "1") (pinfunction "1_1") (pintype "passive"))
      (node (ref "R10") (pin "1") (pinfunction "1_1") (pintype "passive"))
      (node (ref "R9") (pin "2") (pinfunction "2_2") (pintype "passive"))
    )
    (net (code "18") (name "Net-(C6-+)") (class "Default")
      (node (ref "C6") (pin "1") (pinfunction "+_1") (pintype "passive"))
      (node (ref "D2") (pin "2") (pinfunction "C_2") (pintype "passive"))
      (node (ref "R15") (pin "1") (pinfunction "1_1") (pintype "passive"))
      (node (ref "R16") (pin "2") (pinfunction "2_2") (pintype "passive"))
    )
    (net (code "19") (name "Net-(C7-Pad1)") (class "Default")
      (node (ref "C7") (pin "1") (pinfunction "1_1") (pintype "passive"))
      (node (ref "R20") (pin "2") (pinfunction "2_2") (pintype "passive"))
      (node (ref "R21") (pin "1") (pinfunction "1_1") (pintype "passive"))
    )
    (net (code "20") (name "Net-(C10-Pad2)") (class "Default")
      (node (ref "C10") (pin "2") (pinfunction "2_2") (pintype "passive"))
      (node (ref "C9") (pin "1") (pinfunction "1_1") (pintype "passive"))
      (node (ref "R22") (pin "1") (pinfunction "1_1") (pintype "passive"))
    )
    (net (code "21") (name "Net-(C11-+)") (class "Default")
      (node (ref "C11") (pin "1") (pinfunction "+_1") (pintype "passive"))
      (node (ref "D4") (pin "2") (pinfunction "C_2") (pintype "passive"))
      (node (ref "R28") (pin "2") (pinfunction "2_2") (pintype "passive"))
      (node (ref "R30") (pin "1") (pinfunction "1_1") (pintype "passive"))
    )
    (net (code "22") (name "Net-(C12-Pad2)") (class "Default")
      (node (ref "C12") (pin "2") (pinfunction "2_2") (pintype "passive"))
      (node (ref "C13") (pin "1") (pinfunction "1_1") (pintype "passive"))
      (node (ref "R34") (pin "2") (pinfunction "2_2") (pintype "passive"))
    )
    (net (code "23") (name "Net-(C14-+)") (class "Default")
      (node (ref "C14") (pin "1") (pinfunction "+_1") (pintype "passive"))
      (node (ref "D6") (pin "2") (pinfunction "C_2") (pintype "passive"))
      (node (ref "R40") (pin "2") (pinfunction "2_2") (pintype "passive"))
      (node (ref "R41") (pin "2") (pinfunction "2_2") (pintype "passive"))
    )
    (net (code "24") (name "Net-(D1-A)") (class "Default")
      (node (ref "D1") (pin "1") (pinfunction "A_1") (pintype "passive"))
      (node (ref "R33") (pin "1") (pinfunction "1_1") (pintype "passive"))
      (node (ref "U2") (pin "2") (pinfunction "-IN1_2") (pintype "input"))
    )
    (net (code "25") (name "Net-(D1-C)") (class "Default")
      (node (ref "D1") (pin "2") (pinfunction "C_2") (pintype "passive"))
      (node (ref "D2") (pin "1") (pinfunction "A_1") (pintype "passive"))
      (node (ref "U2") (pin "1") (pinfunction "OUT1_1") (pintype "input"))
    )
    (net (code "26") (name "Net-(D3-A)") (class "Default")
      (node (ref "D3") (pin "1") (pinfunction "A_1") (pintype "passive"))
      (node (ref "R45") (pin "1") (pinfunction "1_1") (pintype "passive"))
      (node (ref "U3") (pin "6") (pinfunction "-IN2_6") (pintype "passive"))
    )
    (net (code "27") (name "Net-(D3-C)") (class "Default")
      (node (ref "D3") (pin "2") (pinfunction "C_2") (pintype "passive"))
      (node (ref "D4") (pin "1") (pinfunction "A_1") (pintype "passive"))
      (node (ref "U3") (pin "7") (pinfunction "OUT2_7") (pintype "passive"))
    )
    (net (code "28") (name "Net-(D5-A)") (class "Default")
      (node (ref "D5") (pin "1") (pinfunction "A_1") (pintype "passive"))
      (node (ref "R52") (pin "2") (pinfunction "2_2") (pintype "passive"))
      (node (ref "U5") (pin "13") (pinfunction "-IN4_13") (pintype "bidirectional"))
    )
    (net (code "29") (name "Net-(D5-C)") (class "Default")
      (node (ref "D5") (pin "2") (pinfunction "C_2") (pintype "passive"))
      (node (ref "D6") (pin "1") (pinfunction "A_1") (pintype "passive"))
      (node (ref "U5") (pin "14") (pinfunction "OUT4_14") (pintype "output"))
    )
    (net (code "30") (name "Net-(D7-C)") (class "Default")
      (node (ref "D7") (pin "20") (pinfunction "C_20") (pintype "passive"))
      (node (ref "U7") (pin "10") (pinfunction "LED10_10") (pintype "output"))
    )
    (net (code "31") (name "Net-(D7-C1)") (class "Default")
      (node (ref "D7") (pin "19") (pinfunction "C1_19") (pintype "passive"))
      (node (ref "U7") (pin "11") (pinfunction "LED9_11") (pintype "output"))
    )
    (net (code "32") (name "Net-(D7-C2)") (class "Default")
      (node (ref "D7") (pin "18") (pinfunction "C2_18") (pintype "passive"))
      (node (ref "U7") (pin "12") (pinfunction "LED8_12") (pintype "output"))
    )
    (net (code "33") (name "Net-(D7-C3)") (class "Default")
      (node (ref "D7") (pin "17") (pinfunction "C3_17") (pintype "passive"))
      (node (ref "U7") (pin "13") (pinfunction "LED7_13") (pintype "output"))
    )
    (net (code "34") (name "Net-(D7-C4)") (class "Default")
      (node (ref "D7") (pin "16") (pinfunction "C4_16") (pintype "passive"))
      (node (ref "U7") (pin "14") (pinfunction "LED6_14") (pintype "output"))
    )
    (net (code "35") (name "Net-(D7-C5)") (class "Default")
      (node (ref "D7") (pin "15") (pinfunction "C5_15") (pintype "passive"))
      (node (ref "U7") (pin "15") (pinfunction "LED5_15") (pintype "output"))
    )
    (net (code "36") (name "Net-(D7-C6)") (class "Default")
      (node (ref "D7") (pin "14") (pinfunction "C6_14") (pintype "passive"))
      (node (ref "U7") (pin "16") (pinfunction "LED4_16") (pintype "output"))
    )
    (net (code "37") (name "Net-(D7-C7)") (class "Default")
      (node (ref "D7") (pin "13") (pinfunction "C7_13") (pintype "passive"))
      (node (ref "U7") (pin "17") (pinfunction "LED3_17") (pintype "output"))
    )
    (net (code "38") (name "Net-(D7-C8)") (class "Default")
      (node (ref "D7") (pin "12") (pinfunction "C8_12") (pintype "passive"))
      (node (ref "U7") (pin "18") (pinfunction "LED2_18") (pintype "output"))
    )
    (net (code "39") (name "Net-(D7-C9)") (class "Default")
      (node (ref "D7") (pin "11") (pinfunction "C9_11") (pintype "passive"))
      (node (ref "U7") (pin "1") (pinfunction "LED1_1") (pintype "output"))
    )
    (net (code "40") (name "Net-(D8-C)") (class "Default")
      (node (ref "D8") (pin "20") (pinfunction "C_20") (pintype "passive"))
      (node (ref "U8") (pin "10") (pinfunction "LED10_10") (pintype "output"))
    )
    (net (code "41") (name "Net-(D8-C1)") (class "Default")
      (node (ref "D8") (pin "19") (pinfunction "C1_19") (pintype "passive"))
      (node (ref "U8") (pin "11") (pinfunction "LED9_11") (pintype "output"))
    )
    (net (code "42") (name "Net-(D8-C2)") (class "Default")
      (node (ref "D8") (pin "18") (pinfunction "C2_18") (pintype "passive"))
      (node (ref "U8") (pin "12") (pinfunction "LED8_12") (pintype "output"))
    )
    (net (code "43") (name "Net-(D8-C3)") (class "Default")
      (node (ref "D8") (pin "17") (pinfunction "C3_17") (pintype "passive"))
      (node (ref "U8") (pin "13") (pinfunction "LED7_13") (pintype "output"))
    )
    (net (code "44") (name "Net-(D8-C4)") (class "Default")
      (node (ref "D8") (pin "16") (pinfunction "C4_16") (pintype "passive"))
      (node (ref "U8") (pin "14") (pinfunction "LED6_14") (pintype "output"))
    )
    (net (code "45") (name "Net-(D8-C5)") (class "Default")
      (node (ref "D8") (pin "15") (pinfunction "C5_15") (pintype "passive"))
      (node (ref "U8") (pin "15") (pinfunction "LED5_15") (pintype "output"))
    )
    (net (code "46") (name "Net-(D8-C6)") (class "Default")
      (node (ref "D8") (pin "14") (pinfunction "C6_14") (pintype "passive"))
      (node (ref "U8") (pin "16") (pinfunction "LED4_16") (pintype "output"))
    )
    (net (code "47") (name "Net-(D8-C7)") (class "Default")
      (node (ref "D8") (pin "13") (pinfunction "C7_13") (pintype "passive"))
      (node (ref "U8") (pin "17") (pinfunction "LED3_17") (pintype "output"))
    )
    (net (code "48") (name "Net-(D8-C8)") (class "Default")
      (node (ref "D8") (pin "12") (pinfunction "C8_12") (pintype "passive"))
      (node (ref "U8") (pin "18") (pinfunction "LED2_18") (pintype "output"))
    )
    (net (code "49") (name "Net-(D8-C9)") (class "Default")
      (node (ref "D8") (pin "11") (pinfunction "C9_11") (pintype "passive"))
      (node (ref "U8") (pin "1") (pinfunction "LED1_1") (pintype "output"))
    )
    (net (code "50") (name "Net-(D9-C)") (class "Default")
      (node (ref "D9") (pin "20") (pinfunction "C_20") (pintype "passive"))
      (node (ref "U9") (pin "10") (pinfunction "LED10_10") (pintype "output"))
    )
    (net (code "51") (name "Net-(D9-C1)") (class "Default")
      (node (ref "D9") (pin "19") (pinfunction "C1_19") (pintype "passive"))
      (node (ref "U9") (pin "11") (pinfunction "LED9_11") (pintype "output"))
    )
    (net (code "52") (name "Net-(D9-C2)") (class "Default")
      (node (ref "D9") (pin "18") (pinfunction "C2_18") (pintype "passive"))
      (node (ref "U9") (pin "12") (pinfunction "LED8_12") (pintype "output"))
    )
    (net (code "53") (name "Net-(D9-C3)") (class "Default")
      (node (ref "D9") (pin "17") (pinfunction "C3_17") (pintype "passive"))
      (node (ref "U9") (pin "13") (pinfunction "LED7_13") (pintype "output"))
    )
    (net (code "54") (name "Net-(D9-C4)") (class "Default")
      (node (ref "D9") (pin "16") (pinfunction "C4_16") (pintype "passive"))
      (node (ref "U9") (pin "14") (pinfunction "LED6_14") (pintype "output"))
    )
    (net (code "55") (name "Net-(D9-C5)") (class "Default")
      (node (ref "D9") (pin "15") (pinfunction "C5_15") (pintype "passive"))
      (node (ref "U9") (pin "15") (pinfunction "LED5_15") (pintype "output"))
    )
    (net (code "56") (name "Net-(D9-C6)") (class "Default")
      (node (ref "D9") (pin "14") (pinfunction "C6_14") (pintype "passive"))
      (node (ref "U9") (pin "16") (pinfunction "LED4_16") (pintype "output"))
    )
    (net (code "57") (name "Net-(D9-C7)") (class "Default")
      (node (ref "D9") (pin "13") (pinfunction "C7_13") (pintype "passive"))
      (node (ref "U9") (pin "17") (pinfunction "LED3_17") (pintype "output"))
    )
    (net (code "58") (name "Net-(D9-C8)") (class "Default")
      (node (ref "D9") (pin "12") (pinfunction "C8_12") (pintype "passive"))
      (node (ref "U9") (pin "18") (pinfunction "LED2_18") (pintype "output"))
    )
    (net (code "59") (name "Net-(D9-C9)") (class "Default")
      (node (ref "D9") (pin "11") (pinfunction "C9_11") (pintype "passive"))
      (node (ref "U9") (pin "1") (pinfunction "LED1_1") (pintype "output"))
    )
    (net (code "60") (name "Net-(R1-Pad2)") (class "Default")
      (node (ref "R1") (pin "2") (pinfunction "2_2") (pintype "passive"))
      (node (ref "U$1") (pin "4") (pinfunction "4_4") (pintype "bidirectional"))
    )
    (net (code "61") (name "Net-(R2-Pad2)") (class "Default")
      (node (ref "R2") (pin "2") (pinfunction "2_2") (pintype "passive"))
      (node (ref "U$1") (pin "3") (pinfunction "3_3") (pintype "bidirectional"))
    )
    (net (code "62") (name "Net-(R8-Pad2)") (class "Default")
      (node (ref "R8") (pin "2") (pinfunction "2_2") (pintype "passive"))
      (node (ref "R9") (pin "1") (pinfunction "1_1") (pintype "passive"))
    )
    (net (code "63") (name "Net-(R10-Pad2)") (class "Default")
      (node (ref "R10") (pin "2") (pinfunction "2_2") (pintype "passive"))
      (node (ref "R11") (pin "1") (pinfunction "1_1") (pintype "passive"))
    )
    (net (code "64") (name "Net-(R14-Pad1)") (class "Default")
      (node (ref "R14") (pin "1") (pinfunction "1_1") (pintype "passive"))
      (node (ref "R33") (pin "2") (pinfunction "2_2") (pintype "passive"))
    )
    (net (code "65") (name "Net-(R17_100K-Pad3)") (class "Default")
      (node (ref "R17_100K") (pin "3") (pinfunction "3_3") (pintype "passive"))
      (node (ref "R6") (pin "1") (pinfunction "1_1") (pintype "passive"))
    )
    (net (code "66") (name "Net-(R22-Pad2)") (class "Default")
      (node (ref "R22") (pin "2") (pinfunction "2_2") (pintype "passive"))
      (node (ref "R23") (pin "1") (pinfunction "1_1") (pintype "passive"))
    )
    (net (code "67") (name "Net-(R24-Pad2)") (class "Default")
      (node (ref "R24") (pin "2") (pinfunction "2_2") (pintype "passive"))
      (node (ref "R25") (pin "1") (pinfunction "1_1") (pintype "passive"))
    )
    (net (code "68") (name "Net-(R29-Pad1)") (class "Default")
      (node (ref "R29") (pin "1") (pinfunction "1_1") (pintype "passive"))
      (node (ref "R45") (pin "2") (pinfunction "2_2") (pintype "passive"))
    )
    (net (code "69") (name "Net-(R34-Pad1)") (class "Default")
      (node (ref "R34") (pin "1") (pinfunction "1_1") (pintype "passive"))
      (node (ref "R35") (pin "2") (pinfunction "2_2") (pintype "passive"))
    )
    (net (code "70") (name "Net-(R36-Pad1)") (class "Default")
      (node (ref "R36") (pin "1") (pinfunction "1_1") (pintype "passive"))
      (node (ref "R37") (pin "2") (pinfunction "2_2") (pintype "passive"))
    )
    (net (code "71") (name "Net-(R42-Pad2)") (class "Default")
      (node (ref "R42") (pin "2") (pinfunction "2_2") (pintype "passive"))
      (node (ref "R52") (pin "1") (pinfunction "1_1") (pintype "passive"))
    )
    (net (code "72") (name "Net-(U1-+IN3)") (class "Default")
      (node (ref "C5") (pin "1") (pinfunction "1_1") (pintype "passive"))
      (node (ref "R8") (pin "1") (pinfunction "1_1") (pintype "passive"))
      (node (ref "U1") (pin "10") (pinfunction "+IN3_10") (pintype "passive"))
    )
    (net (code "73") (name "Net-(U1-+IN4)") (class "Default")
      (node (ref "R6") (pin "2") (pinfunction "2_2") (pintype "passive"))
      (node (ref "U1") (pin "12") (pinfunction "+IN4_12") (pintype "bidirectional"))
      (node (ref "U1") (pin "7") (pinfunction "OUT2_7") (pintype "passive"))
    )
    (net (code "74") (name "Net-(U1--IN2)") (class "Default")
      (node (ref "R17_100K") (pin "2") (pinfunction "2_2") (pintype "passive"))
      (node (ref "R7") (pin "2") (pinfunction "2_2") (pintype "passive"))
      (node (ref "U1") (pin "6") (pinfunction "-IN2_6") (pintype "passive"))
    )
    (net (code "75") (name "Net-(U1--IN3)") (class "Default")
      (node (ref "R12") (pin "2") (pinfunction "2_2") (pintype "passive"))
      (node (ref "R13") (pin "1") (pinfunction "1_1") (pintype "passive"))
      (node (ref "U1") (pin "9") (pinfunction "-IN3_9") (pintype "passive"))
    )
    (net (code "76") (name "Net-(U2-+IN2)") (class "Default")
      (node (ref "R15") (pin "2") (pinfunction "2_2") (pintype "passive"))
      (node (ref "U2") (pin "5") (pinfunction "+IN2_5") (pintype "passive"))
    )
    (net (code "77") (name "Net-(U2-+IN3)") (class "Default")
      (node (ref "U2") (pin "10") (pinfunction "+IN3_10") (pintype "passive"))
      (node (ref "U2") (pin "13") (pinfunction "-IN4_13") (pintype "bidirectional"))
      (node (ref "U2") (pin "14") (pinfunction "OUT4_14") (pintype "output"))
    )
    (net (code "78") (name "Net-(U2--IN3)") (class "Default")
      (node (ref "R19") (pin "1") (pinfunction "1_1") (pintype "passive"))
      (node (ref "U2") (pin "9") (pinfunction "-IN3_9") (pintype "passive"))
      (node (ref "VR2") (pin "3") (pinfunction "CW_3") (pintype "passive"))
    )
    (net (code "79") (name "Net-(U3-+IN3)") (class "Default")
      (node (ref "C8") (pin "1") (pinfunction "1_1") (pintype "passive"))
      (node (ref "R20") (pin "1") (pinfunction "1_1") (pintype "passive"))
      (node (ref "U3") (pin "10") (pinfunction "+IN3_10") (pintype "passive"))
    )
    (net (code "80") (name "Net-(U3-+IN4)") (class "Default")
      (node (ref "C9") (pin "2") (pinfunction "2_2") (pintype "passive"))
      (node (ref "R24") (pin "1") (pinfunction "1_1") (pintype "passive"))
      (node (ref "U3") (pin "12") (pinfunction "+IN4_12") (pintype "bidirectional"))
    )
    (net (code "81") (name "Net-(U3--IN4)") (class "Default")
      (node (ref "R26") (pin "2") (pinfunction "2_2") (pintype "passive"))
      (node (ref "R27") (pin "1") (pinfunction "1_1") (pintype "passive"))
      (node (ref "U3") (pin "13") (pinfunction "-IN4_13") (pintype "bidirectional"))
    )
    (net (code "82") (name "Net-(U3-OUT4)") (class "Default")
      (node (ref "R21") (pin "2") (pinfunction "2_2") (pintype "passive"))
      (node (ref "R23") (pin "2") (pinfunction "2_2") (pintype "passive"))
      (node (ref "R26") (pin "1") (pinfunction "1_1") (pintype "passive"))
      (node (ref "U3") (pin "14") (pinfunction "OUT4_14") (pintype "output"))
    )
    (net (code "83") (name "Net-(U4-+IN1)") (class "Default")
      (node (ref "R30") (pin "2") (pinfunction "2_2") (pintype "passive"))
      (node (ref "U4") (pin "3") (pinfunction "+IN1_3") (pintype "bidirectional"))
    )
    (net (code "84") (name "Net-(U4-+IN2)") (class "Default")
      (node (ref "R54") (pin "1") (pinfunction "1_1") (pintype "passive"))
      (node (ref "U4") (pin "5") (pinfunction "+IN2_5") (pintype "passive"))
    )
    (net (code "85") (name "Net-(U4-+IN3)") (class "Default")
      (node (ref "U4") (pin "10") (pinfunction "+IN3_10") (pintype "passive"))
      (node (ref "U4") (pin "6") (pinfunction "-IN2_6") (pintype "passive"))
      (node (ref "U4") (pin "7") (pinfunction "OUT2_7") (pintype "passive"))
    )
    (net (code "86") (name "Net-(U4--IN1)") (class "Default")
      (node (ref "R29") (pin "2") (pinfunction "2_2") (pintype "passive"))
      (node (ref "R54") (pin "2") (pinfunction "2_2") (pintype "passive"))
      (node (ref "U4") (pin "1") (pinfunction "OUT1_1") (pintype "input"))
      (node (ref "U4") (pin "2") (pinfunction "-IN1_2") (pintype "input"))
    )
    (net (code "87") (name "Net-(U4--IN3)") (class "Default")
      (node (ref "R31") (pin "1") (pinfunction "1_1") (pintype "passive"))
      (node (ref "U4") (pin "9") (pinfunction "-IN3_9") (pintype "passive"))
      (node (ref "VR3") (pin "3") (pinfunction "CW_3") (pintype "passive"))
    )
    (net (code "88") (name "Net-(U4--IN4)") (class "Default")
      (node (ref "U4") (pin "13") (pinfunction "-IN4_13") (pintype "bidirectional"))
      (node (ref "U4") (pin "14") (pinfunction "OUT4_14") (pintype "output"))
    )
    (net (code "89") (name "Net-(U5-+IN2)") (class "Default")
      (node (ref "C12") (pin "1") (pinfunction "1_1") (pintype "passive"))
      (node (ref "R36") (pin "2") (pinfunction "2_2") (pintype "passive"))
      (node (ref "U5") (pin "5") (pinfunction "+IN2_5") (pintype "passive"))
    )
    (net (code "90") (name "Net-(U5-+IN3)") (class "Default")
      (node (ref "R41") (pin "1") (pinfunction "1_1") (pintype "passive"))
      (node (ref "U5") (pin "10") (pinfunction "+IN3_10") (pintype "passive"))
    )
    (net (code "91") (name "Net-(U5--IN2)") (class "Default")
      (node (ref "R38") (pin "1") (pinfunction "1_1") (pintype "passive"))
      (node (ref "R39") (pin "2") (pinfunction "2_2") (pintype "passive"))
      (node (ref "U5") (pin "6") (pinfunction "-IN2_6") (pintype "passive"))
    )
    (net (code "92") (name "Net-(U6-+IN3)") (class "Default")
      (node (ref "U6") (pin "10") (pinfunction "+IN3_10") (pintype "passive"))
      (node (ref "U6") (pin "13") (pinfunction "-IN4_13") (pintype "bidirectional"))
      (node (ref "U6") (pin "14") (pinfunction "OUT4_14") (pintype "output"))
    )
    (net (code "93") (name "Net-(U6--IN1)") (class "Default")
      (node (ref "U6") (pin "1") (pinfunction "OUT1_1") (pintype "input"))
      (node (ref "U6") (pin "2") (pinfunction "-IN1_2") (pintype "input"))
    )
    (net (code "94") (name "Net-(U6--IN2)") (class "Default")
      (node (ref "U6") (pin "6") (pinfunction "-IN2_6") (pintype "passive"))
      (node (ref "U6") (pin "7") (pinfunction "OUT2_7") (pintype "passive"))
    )
    (net (code "95") (name "Net-(U6--IN3)") (class "Default")
      (node (ref "R43") (pin "1") (pinfunction "1_1") (pintype "passive"))
      (node (ref "U6") (pin "9") (pinfunction "-IN3_9") (pintype "passive"))
      (node (ref "VR4") (pin "3") (pinfunction "CW_3") (pintype "passive"))
    )
    (net (code "96") (name "Net-(U7-REFADJ)") (class "Default")
      (node (ref "R46") (pin "1") (pinfunction "1_1") (pintype "passive"))
      (node (ref "R47") (pin "2") (pinfunction "2_2") (pintype "passive"))
      (node (ref "U7") (pin "8") (pinfunction "REFADJ_8") (pintype "passive"))
    )
    (net (code "97") (name "Net-(U7-REFOUT)") (class "Default")
      (node (ref "R46") (pin "2") (pinfunction "2_2") (pintype "passive"))
      (node (ref "U7") (pin "6") (pinfunction "RHI_6") (pintype "input"))
      (node (ref "U7") (pin "7") (pinfunction "REFOUT_7") (pintype "output"))
    )
    (net (code "98") (name "Net-(U8-REFADJ)") (class "Default")
      (node (ref "R48") (pin "1") (pinfunction "1_1") (pintype "passive"))
      (node (ref "R49") (pin "2") (pinfunction "2_2") (pintype "passive"))
      (node (ref "U8") (pin "8") (pinfunction "REFADJ_8") (pintype "passive"))
    )
    (net (code "99") (name "Net-(U8-REFOUT)") (class "Default")
      (node (ref "R48") (pin "2") (pinfunction "2_2") (pintype "passive"))
      (node (ref "U8") (pin "6") (pinfunction "RHI_6") (pintype "input"))
      (node (ref "U8") (pin "7") (pinfunction "REFOUT_7") (pintype "output"))
    )
    (net (code "100") (name "Net-(U9-REFADJ)") (class "Default")
      (node (ref "R50") (pin "1") (pinfunction "1_1") (pintype "passive"))
      (node (ref "R51") (pin "2") (pinfunction "2_2") (pintype "passive"))
      (node (ref "U9") (pin "8") (pinfunction "REFADJ_8") (pintype "passive"))
    )
    (net (code "101") (name "Net-(U9-REFOUT)") (class "Default")
      (node (ref "R50") (pin "2") (pinfunction "2_2") (pintype "passive"))
      (node (ref "U9") (pin "6") (pinfunction "RHI_6") (pintype "input"))
      (node (ref "U9") (pin "7") (pinfunction "REFOUT_7") (pintype "output"))
    )
    (net (code "102") (name "Net-(VR2-WIPER)") (class "Default")
      (node (ref "R18") (pin "1") (pinfunction "1_1") (pintype "passive"))
      (node (ref "VR2") (pin "2") (pinfunction "WIPER_2") (pintype "passive"))
    )
    (net (code "103") (name "Net-(VR3-WIPER)") (class "Default")
      (node (ref "R32") (pin "1") (pinfunction "1_1") (pintype "passive"))
      (node (ref "VR3") (pin "2") (pinfunction "WIPER_2") (pintype "passive"))
    )
    (net (code "104") (name "Net-(VR4-WIPER)") (class "Default")
      (node (ref "R44") (pin "1") (pinfunction "1_1") (pintype "passive"))
      (node (ref "VR4") (pin "2") (pinfunction "WIPER_2") (pintype "passive"))
    )
    (net (code "105") (name "VMID") (class "Default")
      (node (ref "9V_IN") (pin "1") (pinfunction "1_1") (pintype "bidirectional"))
      (node (ref "C11") (pin "2") (pinfunction "-_2") (pintype "passive"))
      (node (ref "C14") (pin "2") (pinfunction "-_2") (pintype "passive"))
      (node (ref "C2") (pin "2") (pinfunction "2_2") (pintype "passive"))
      (node (ref "C3") (pin "1") (pinfunction "+_1") (pintype "passive"))
      (node (ref "C5") (pin "2") (pinfunction "2_2") (pintype "passive"))
      (node (ref "C6") (pin "2") (pinfunction "-_2") (pintype "passive"))
      (node (ref "C8") (pin "2") (pinfunction "2_2") (pintype "passive"))
      (node (ref "R13") (pin "2") (pinfunction "2_2") (pintype "passive"))
      (node (ref "R16") (pin "1") (pinfunction "1_1") (pintype "passive"))
      (node (ref "R19") (pin "2") (pinfunction "2_2") (pintype "passive"))
      (node (ref "R25") (pin "2") (pinfunction "2_2") (pintype "passive"))
      (node (ref "R27") (pin "2") (pinfunction "2_2") (pintype "passive"))
      (node (ref "R28") (pin "1") (pinfunction "1_1") (pintype "passive"))
      (node (ref "R3") (pin "2") (pinfunction "2_2") (pintype "passive"))
      (node (ref "R31") (pin "2") (pinfunction "2_2") (pintype "passive"))
      (node (ref "R37") (pin "1") (pinfunction "1_1") (pintype "passive"))
      (node (ref "R39") (pin "1") (pinfunction "1_1") (pintype "passive"))
      (node (ref "R40") (pin "1") (pinfunction "1_1") (pintype "passive"))
      (node (ref "R43") (pin "2") (pinfunction "2_2") (pintype "passive"))
      (node (ref "R47") (pin "1") (pinfunction "1_1") (pintype "passive"))
      (node (ref "R49") (pin "1") (pinfunction "1_1") (pintype "passive"))
      (node (ref "R51") (pin "1") (pinfunction "1_1") (pintype "passive"))
      (node (ref "R7") (pin "1") (pinfunction "1_1") (pintype "passive"))
      (node (ref "U1") (pin "1") (pinfunction "OUT1_1") (pintype "input"))
      (node (ref "U1") (pin "2") (pinfunction "-IN1_2") (pintype "input"))
      (node (ref "U4") (pin "12") (pinfunction "+IN4_12") (pintype "bidirectional"))
      (node (ref "U6") (pin "3") (pinfunction "+IN1_3") (pintype "bidirectional"))
      (node (ref "U6") (pin "5") (pinfunction "+IN2_5") (pintype "passive"))
      (node (ref "U7") (pin "4") (pinfunction "RLO_4") (pintype "input"))
      (node (ref "U8") (pin "4") (pinfunction "RLO_4") (pintype "input"))
      (node (ref "U9") (pin "4") (pinfunction "RLO_4") (pintype "input"))
    )
    (net (code "106") (name "unconnected-(R17_100K-Pad1)") (class "Default")
      (node (ref "R17_100K") (pin "1") (pinfunction "1_1") (pintype "passive"))
    )
    (net (code "107") (name "unconnected-(VR2-CCW-Pad1)") (class "Default")
      (node (ref "VR2") (pin "1") (pinfunction "CCW_1") (pintype "passive"))
    )
    (net (code "108") (name "unconnected-(VR3-CCW-Pad1)") (class "Default")
      (node (ref "VR3") (pin "1") (pinfunction "CCW_1") (pintype "passive"))
    )
    (net (code "109") (name "unconnected-(VR4-CCW-Pad1)") (class "Default")
      (node (ref "VR4") (pin "1") (pinfunction "CCW_1") (pintype "passive"))
    )
  )
)
